# watch.net
KiCad netlist of a schematic drawn in EAGLE
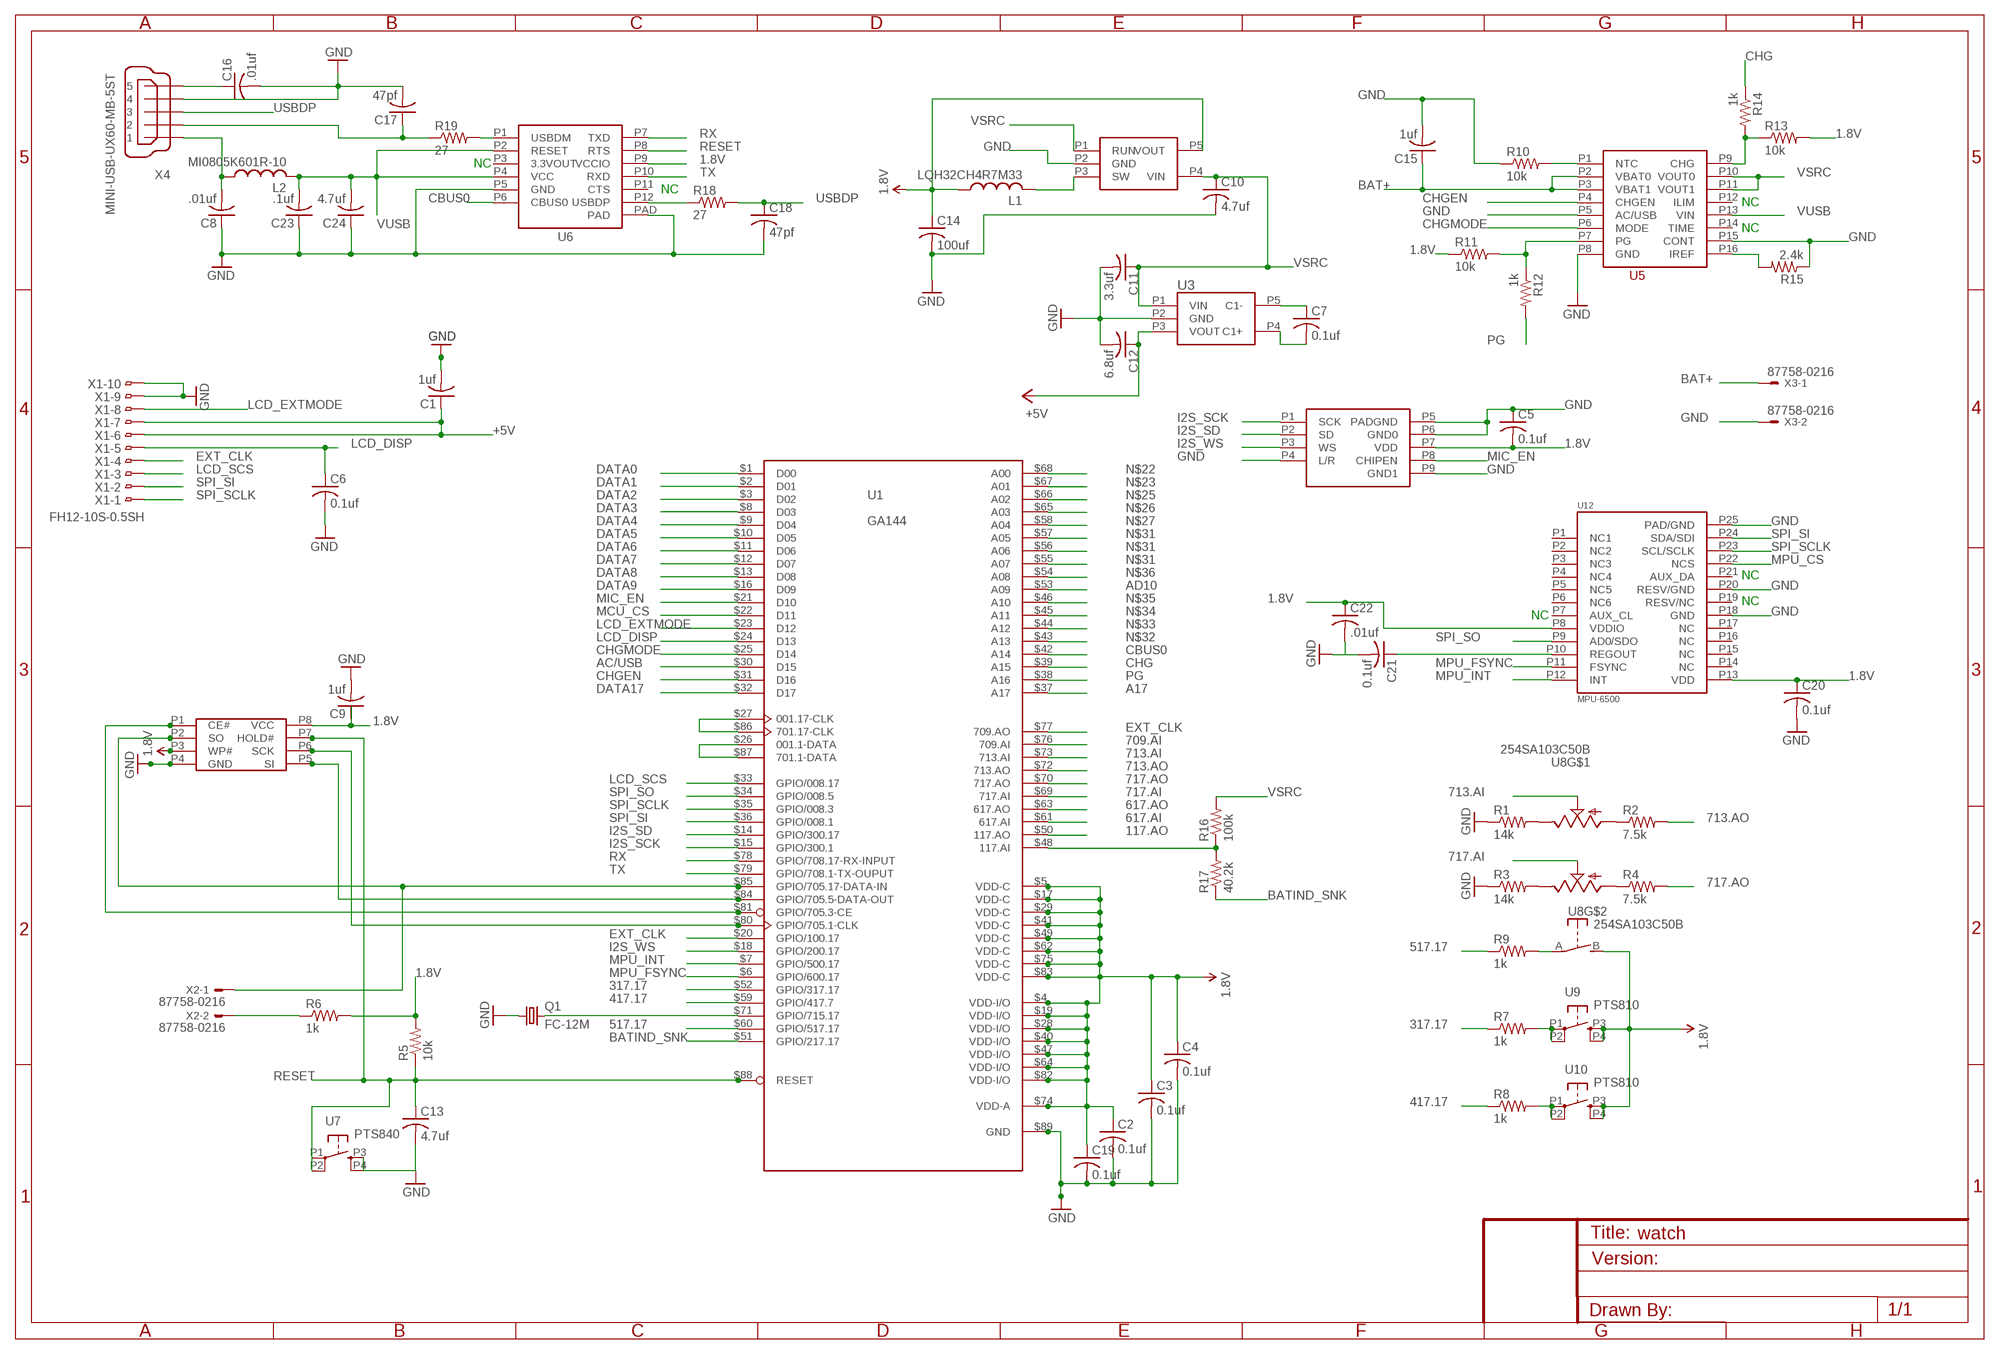
[diagram p0: schematic, sheet 1]

(export (version "E")
  (design (tool "Eeschema 10.0.6"))
  (components
    (comp (ref "C1")
      (value "1uf")
      (footprint "eagle-import:C0402")
      (libsource (lib "eagle-import") (part "resistor_C-USC0402"))
    )
    (comp (ref "C2")
      (value "0.1uf")
      (footprint "eagle-import:C0402")
      (libsource (lib "eagle-import") (part "resistor_C-USC0402"))
    )
    (comp (ref "C3")
      (value "0.1uf")
      (footprint "eagle-import:C0402")
      (libsource (lib "eagle-import") (part "resistor_C-USC0402"))
    )
    (comp (ref "C4")
      (value "0.1uf")
      (footprint "eagle-import:C0402")
      (libsource (lib "eagle-import") (part "resistor_C-USC0402"))
    )
    (comp (ref "C5")
      (value "0.1uf")
      (footprint "eagle-import:C0402")
      (libsource (lib "eagle-import") (part "resistor_C-USC0402"))
    )
    (comp (ref "C6")
      (value "0.1uf")
      (footprint "eagle-import:C0402")
      (libsource (lib "eagle-import") (part "resistor_C-USC0402"))
    )
    (comp (ref "C7")
      (value "0.1uf")
      (footprint "eagle-import:C0402")
      (libsource (lib "eagle-import") (part "resistor_C-USC0402"))
    )
    (comp (ref "C8")
      (value ".01uf")
      (footprint "eagle-import:C0402")
      (libsource (lib "eagle-import") (part "resistor_C-USC0402"))
    )
    (comp (ref "C9")
      (value "1uf")
      (footprint "eagle-import:C0402")
      (libsource (lib "eagle-import") (part "resistor_C-USC0402"))
    )
    (comp (ref "C10")
      (value "4.7uf")
      (footprint "eagle-import:C0603")
      (libsource (lib "eagle-import") (part "resistor_C-USC0603"))
    )
    (comp (ref "C11")
      (value "3.3uf")
      (footprint "eagle-import:C0603")
      (libsource (lib "eagle-import") (part "resistor_C-USC0603"))
    )
    (comp (ref "C12")
      (value "6.8uf")
      (footprint "eagle-import:C0805")
      (libsource (lib "eagle-import") (part "resistor_C-USC0805"))
    )
    (comp (ref "C13")
      (value "4.7uf")
      (footprint "eagle-import:C0603")
      (libsource (lib "eagle-import") (part "resistor_C-USC0603"))
    )
    (comp (ref "C14")
      (value "100uf")
      (footprint "eagle-import:C1206")
      (libsource (lib "eagle-import") (part "C-USC1206"))
    )
    (comp (ref "C15")
      (value "1uf")
      (footprint "eagle-import:C0402")
      (libsource (lib "eagle-import") (part "resistor_C-USC0402"))
    )
    (comp (ref "C16")
      (value ".01uf")
      (footprint "eagle-import:C0402")
      (libsource (lib "eagle-import") (part "resistor_C-USC0402"))
    )
    (comp (ref "C17")
      (value "47pf")
      (footprint "eagle-import:C0402")
      (libsource (lib "eagle-import") (part "resistor_C-USC0402"))
    )
    (comp (ref "C18")
      (value "47pf")
      (footprint "eagle-import:C0402")
      (libsource (lib "eagle-import") (part "resistor_C-USC0402"))
    )
    (comp (ref "C19")
      (value "0.1uf")
      (footprint "eagle-import:C0402")
      (libsource (lib "eagle-import") (part "resistor_C-USC0402"))
    )
    (comp (ref "C20")
      (value "0.1uf")
      (footprint "eagle-import:C0402")
      (libsource (lib "eagle-import") (part "resistor_C-USC0402"))
    )
    (comp (ref "C21")
      (value "0.1uf")
      (footprint "eagle-import:C0402")
      (libsource (lib "eagle-import") (part "resistor_C-USC0402"))
    )
    (comp (ref "C22")
      (value ".01uf")
      (footprint "eagle-import:C0402")
      (libsource (lib "eagle-import") (part "resistor_C-USC0402"))
    )
    (comp (ref "C23")
      (value ".1uf")
      (footprint "eagle-import:C0402")
      (libsource (lib "eagle-import") (part "resistor_C-USC0402"))
    )
    (comp (ref "C24")
      (value "4.7uf")
      (footprint "eagle-import:C0402")
      (libsource (lib "eagle-import") (part "resistor_C-USC0402"))
    )
    (comp (ref "L1")
      (value "LQH32CH4R7M33")
      (footprint "eagle-import:1210")
      (libsource (lib "eagle-import") (part "LQH32CH4R7M33"))
    )
    (comp (ref "L2")
      (value "MI0805K601R-10")
      (footprint "eagle-import:C0805")
      (libsource (lib "eagle-import") (part "MI0805K601R-10"))
    )
    (comp (ref "Q1")
      (value "FC-12M")
      (footprint "eagle-import:FC-12M")
      (libsource (lib "eagle-import") (part "FC-12M"))
    )
    (comp (ref "R1")
      (value "14k")
      (footprint "eagle-import:R0402")
      (libsource (lib "eagle-import") (part "R-US_R0402"))
    )
    (comp (ref "R2")
      (value "7.5k")
      (footprint "eagle-import:R0402")
      (libsource (lib "eagle-import") (part "R-US_R0402"))
    )
    (comp (ref "R3")
      (value "14k")
      (footprint "eagle-import:R0402")
      (libsource (lib "eagle-import") (part "R-US_R0402"))
    )
    (comp (ref "R4")
      (value "7.5k")
      (footprint "eagle-import:R0402")
      (libsource (lib "eagle-import") (part "R-US_R0402"))
    )
    (comp (ref "R5")
      (value "10k")
      (footprint "eagle-import:R0402")
      (libsource (lib "eagle-import") (part "R-US_R0402"))
    )
    (comp (ref "R6")
      (value "1k")
      (footprint "eagle-import:R0402")
      (libsource (lib "eagle-import") (part "R-US_R0402"))
    )
    (comp (ref "R7")
      (value "1k")
      (footprint "eagle-import:R0402")
      (libsource (lib "eagle-import") (part "R-US_R0402"))
    )
    (comp (ref "R8")
      (value "1k")
      (footprint "eagle-import:R0402")
      (libsource (lib "eagle-import") (part "R-US_R0402"))
    )
    (comp (ref "R9")
      (value "1k")
      (footprint "eagle-import:R0402")
      (libsource (lib "eagle-import") (part "R-US_R0402"))
    )
    (comp (ref "R10")
      (value "10k")
      (footprint "eagle-import:R0402")
      (libsource (lib "eagle-import") (part "R-US_R0402"))
    )
    (comp (ref "R11")
      (value "10k")
      (footprint "eagle-import:R0402")
      (libsource (lib "eagle-import") (part "R-US_R0402"))
    )
    (comp (ref "R12")
      (value "1k")
      (footprint "eagle-import:R0402")
      (libsource (lib "eagle-import") (part "R-US_R0402"))
    )
    (comp (ref "R13")
      (value "10k")
      (footprint "eagle-import:R0402")
      (libsource (lib "eagle-import") (part "R-US_R0402"))
    )
    (comp (ref "R14")
      (value "1k")
      (footprint "eagle-import:R0402")
      (libsource (lib "eagle-import") (part "R-US_R0402"))
    )
    (comp (ref "R15")
      (value "2.4k")
      (footprint "eagle-import:R0402")
      (libsource (lib "eagle-import") (part "R-US_R0402"))
    )
    (comp (ref "R16")
      (value "100k")
      (footprint "eagle-import:R0402")
      (libsource (lib "eagle-import") (part "R-US_R0402"))
    )
    (comp (ref "R17")
      (value "40.2k")
      (footprint "eagle-import:R0402")
      (libsource (lib "eagle-import") (part "R-US_R0402"))
    )
    (comp (ref "R18")
      (value "27")
      (footprint "eagle-import:R0402")
      (libsource (lib "eagle-import") (part "R-US_R0402"))
    )
    (comp (ref "R19")
      (value "27")
      (footprint "eagle-import:R0402")
      (libsource (lib "eagle-import") (part "R-US_R0402"))
    )
    (comp (ref "U1")
      (value "GA144")
      (footprint "eagle-import:QFN88-0.4MM")
      (libsource (lib "eagle-import") (part "GA144"))
    )
    (comp (ref "U2")
      (value "LTC3406-1.8")
      (footprint "eagle-import:TSOT23")
      (libsource (lib "eagle-import") (part "LTC3406-1.8"))
    )
    (comp (ref "U3")
      (value "LTC1517-5")
      (footprint "eagle-import:TSOT23")
      (libsource (lib "eagle-import") (part "LTC1517-5"))
    )
    (comp (ref "U4")
      (value "IS25WP128-JKLE")
      (footprint "eagle-import:WSON8")
      (libsource (lib "eagle-import") (part "IS25WP128-JKLE"))
    )
    (comp (ref "U5")
      (value "ISL9230")
      (footprint "eagle-import:16_LD_QFN")
      (libsource (lib "eagle-import") (part "ISL9230"))
    )
    (comp (ref "U6")
      (value "FT234XD")
      (footprint "eagle-import:DFN-12")
      (libsource (lib "eagle-import") (part "FT234XD"))
    )
    (comp (ref "U7")
      (value "PTS840")
      (footprint "eagle-import:PTS840GMPSMTRLFS")
      (libsource (lib "eagle-import") (part "PTS840"))
    )
    (comp (ref "U8")
      (value "254SA103C50B")
      (footprint "eagle-import:254SA103C50B")
      (libsource (lib "eagle-import") (part "254SA103C50B"))
    )
    (comp (ref "U9")
      (value "PTS810")
      (footprint "eagle-import:PTS810")
      (libsource (lib "eagle-import") (part "PTS810"))
    )
    (comp (ref "U10")
      (value "PTS810")
      (footprint "eagle-import:PTS810")
      (libsource (lib "eagle-import") (part "PTS810"))
    )
    (comp (ref "U11")
      (value "INMP441")
      (footprint "eagle-import:INMP441")
      (libsource (lib "eagle-import") (part "INMP441"))
    )
    (comp (ref "U12")
      (value "MPU-6500")
      (footprint "eagle-import:QFN24-3")
      (libsource (lib "eagle-import") (part "MPU-6500"))
    )
    (comp (ref "X1")
      (value "FH12-10S-0.5SH")
      (footprint "eagle-import:FH12-10S-0.5SH")
      (fields (field (name "MPN") "FH12-10S-0.5SH(55)"))
      (libsource (lib "eagle-import") (part "FH12-10S-0.5SH"))
    )
    (comp (ref "X2")
      (value "87758-0216")
      (footprint "eagle-import:87758-0216")
      (libsource (lib "eagle-import") (part "87758-0216"))
    )
    (comp (ref "X3")
      (value "87758-0216")
      (footprint "eagle-import:87758-0216")
      (libsource (lib "eagle-import") (part "87758-0216"))
    )
    (comp (ref "X4")
      (value "MINI-USB-UX60-MB-5ST")
      (footprint "eagle-import:UX60-MB-5ST")
      (libsource (lib "eagle-import") (part "MINI-USB-UX60-MB-5ST"))
    )
  )
  (nets
    (net (code "1") (name "+5V") (class "Default")
      (node (ref "C1") (pin "1") (pinfunction "1_1") (pintype "passive"))
      (node (ref "C12") (pin "1") (pinfunction "1_1") (pintype "passive"))
      (node (ref "U3") (pin "P3") (pinfunction "VOUT_P3") (pintype "bidirectional"))
      (node (ref "X1") (pin "6") (pinfunction "1_6") (pintype "passive"))
      (node (ref "X1") (pin "7") (pinfunction "1_7") (pintype "passive"))
    )
    (net (code "2") (name "/117.AO") (class "Default")
      (node (ref "U1") (pin "$50") (pinfunction "117.AO_$50") (pintype "output"))
    )
    (net (code "3") (name "/317.17") (class "Default")
      (node (ref "R7") (pin "1") (pinfunction "1_1") (pintype "passive"))
      (node (ref "U1") (pin "$52") (pinfunction "GPIO/317.17_$52") (pintype "bidirectional"))
    )
    (net (code "4") (name "/417.17") (class "Default")
      (node (ref "R8") (pin "1") (pinfunction "1_1") (pintype "passive"))
      (node (ref "U1") (pin "$59") (pinfunction "GPIO/417.7_$59") (pintype "bidirectional"))
    )
    (net (code "5") (name "/517.17") (class "Default")
      (node (ref "R9") (pin "1") (pinfunction "1_1") (pintype "passive"))
      (node (ref "U1") (pin "$60") (pinfunction "GPIO/517.17_$60") (pintype "bidirectional"))
    )
    (net (code "6") (name "/617.AI") (class "Default")
      (node (ref "U1") (pin "$61") (pinfunction "617.AI_$61") (pintype "input"))
    )
    (net (code "7") (name "/617.AO") (class "Default")
      (node (ref "U1") (pin "$63") (pinfunction "617.AO_$63") (pintype "output"))
    )
    (net (code "8") (name "/709.AI") (class "Default")
      (node (ref "U1") (pin "$76") (pinfunction "709.AI_$76") (pintype "input"))
    )
    (net (code "9") (name "/713.AI") (class "Default")
      (node (ref "U1") (pin "$73") (pinfunction "713.AI_$73") (pintype "input"))
      (node (ref "U8") (pin "P2") (pinfunction "P2_P2") (pintype "passive"))
    )
    (net (code "10") (name "/713.AO") (class "Default")
      (node (ref "R2") (pin "2") (pinfunction "2_2") (pintype "passive"))
      (node (ref "U1") (pin "$72") (pinfunction "713.AO_$72") (pintype "output"))
    )
    (net (code "11") (name "/717.AI") (class "Default")
      (node (ref "U1") (pin "$69") (pinfunction "717.AI_$69") (pintype "input"))
      (node (ref "U8") (pin "P2'") (pinfunction "P2'_P2'") (pintype "passive"))
    )
    (net (code "12") (name "/717.AO") (class "Default")
      (node (ref "R4") (pin "2") (pinfunction "2_2") (pintype "passive"))
      (node (ref "U1") (pin "$70") (pinfunction "717.AO_$70") (pintype "output"))
    )
    (net (code "13") (name "/A17") (class "Default")
      (node (ref "U1") (pin "$37") (pinfunction "A17_$37") (pintype "output"))
    )
    (net (code "14") (name "/AC{slash}USB") (class "Default")
      (node (ref "U1") (pin "$30") (pinfunction "D15_$30") (pintype "bidirectional"))
    )
    (net (code "15") (name "/AD10") (class "Default")
      (node (ref "U1") (pin "$53") (pinfunction "A09_$53") (pintype "output"))
    )
    (net (code "16") (name "/AUX_CL") (class "Default")
      (node (ref "U12") (pin "P7") (pinfunction "AUX_CL_P7") (pintype "power_in"))
    )
    (net (code "17") (name "/AUX_DA") (class "Default")
      (node (ref "U12") (pin "P21") (pinfunction "AUX_DA_P21") (pintype "power_in"))
    )
    (net (code "18") (name "/BAT+") (class "Default")
      (node (ref "C15") (pin "1") (pinfunction "1_1") (pintype "passive"))
      (node (ref "U5") (pin "P2") (pinfunction "VBAT0_P2") (pintype "bidirectional"))
      (node (ref "U5") (pin "P3") (pinfunction "VBAT1_P3") (pintype "bidirectional"))
      (node (ref "X3") (pin "1") (pinfunction "S_1") (pintype "passive"))
    )
    (net (code "19") (name "/BATIND_SNK") (class "Default")
      (node (ref "R17") (pin "1") (pinfunction "1_1") (pintype "passive"))
      (node (ref "U1") (pin "$51") (pinfunction "GPIO/217.17_$51") (pintype "bidirectional"))
    )
    (net (code "20") (name "/CBUS0") (class "Default")
      (node (ref "U1") (pin "$42") (pinfunction "A14_$42") (pintype "output"))
      (node (ref "U6") (pin "P6") (pinfunction "CBUS0_P6") (pintype "bidirectional"))
    )
    (net (code "21") (name "/CHG") (class "Default")
      (node (ref "R14") (pin "1") (pinfunction "1_1") (pintype "passive"))
      (node (ref "U1") (pin "$39") (pinfunction "A15_$39") (pintype "output"))
    )
    (net (code "22") (name "/CHGEN") (class "Default")
      (node (ref "U1") (pin "$31") (pinfunction "D16_$31") (pintype "bidirectional"))
      (node (ref "U5") (pin "P4") (pinfunction "CHGEN_P4") (pintype "bidirectional"))
    )
    (net (code "23") (name "/CHGMODE") (class "Default")
      (node (ref "U1") (pin "$25") (pinfunction "D14_$25") (pintype "bidirectional"))
      (node (ref "U5") (pin "P6") (pinfunction "MODE_P6") (pintype "bidirectional"))
    )
    (net (code "24") (name "/DATA0") (class "Default")
      (node (ref "U1") (pin "$1") (pinfunction "D00_$1") (pintype "bidirectional"))
    )
    (net (code "25") (name "/DATA1") (class "Default")
      (node (ref "U1") (pin "$2") (pinfunction "D01_$2") (pintype "bidirectional"))
    )
    (net (code "26") (name "/DATA2") (class "Default")
      (node (ref "U1") (pin "$3") (pinfunction "D02_$3") (pintype "bidirectional"))
    )
    (net (code "27") (name "/DATA3") (class "Default")
      (node (ref "U1") (pin "$8") (pinfunction "D03_$8") (pintype "bidirectional"))
    )
    (net (code "28") (name "/DATA4") (class "Default")
      (node (ref "U1") (pin "$9") (pinfunction "D04_$9") (pintype "bidirectional"))
    )
    (net (code "29") (name "/DATA5") (class "Default")
      (node (ref "U1") (pin "$10") (pinfunction "D05_$10") (pintype "bidirectional"))
    )
    (net (code "30") (name "/DATA6") (class "Default")
      (node (ref "U1") (pin "$11") (pinfunction "D06_$11") (pintype "bidirectional"))
    )
    (net (code "31") (name "/DATA7") (class "Default")
      (node (ref "U1") (pin "$12") (pinfunction "D07_$12") (pintype "bidirectional"))
    )
    (net (code "32") (name "/DATA8") (class "Default")
      (node (ref "U1") (pin "$13") (pinfunction "D08_$13") (pintype "bidirectional"))
    )
    (net (code "33") (name "/DATA9") (class "Default")
      (node (ref "U1") (pin "$16") (pinfunction "D09_$16") (pintype "bidirectional"))
    )
    (net (code "34") (name "/DATA17") (class "Default")
      (node (ref "U1") (pin "$32") (pinfunction "D17_$32") (pintype "bidirectional"))
    )
    (net (code "35") (name "/EXT_CLK") (class "Default")
      (node (ref "U1") (pin "$20") (pinfunction "GPIO/100.17_$20") (pintype "bidirectional"))
      (node (ref "U1") (pin "$77") (pinfunction "709.AO_$77") (pintype "output"))
      (node (ref "X1") (pin "4") (pinfunction "1_4") (pintype "passive"))
    )
    (net (code "36") (name "/I2S_SCK") (class "Default")
      (node (ref "U1") (pin "$15") (pinfunction "GPIO/300.1_$15") (pintype "bidirectional"))
      (node (ref "U11") (pin "P1") (pinfunction "SCK_P1") (pintype "bidirectional"))
    )
    (net (code "37") (name "/I2S_SD") (class "Default")
      (node (ref "U1") (pin "$14") (pinfunction "GPIO/300.17_$14") (pintype "bidirectional"))
      (node (ref "U11") (pin "P2") (pinfunction "SD_P2") (pintype "bidirectional"))
    )
    (net (code "38") (name "/I2S_WS") (class "Default")
      (node (ref "U1") (pin "$18") (pinfunction "GPIO/200.17_$18") (pintype "bidirectional"))
      (node (ref "U11") (pin "P3") (pinfunction "WS_P3") (pintype "bidirectional"))
    )
    (net (code "39") (name "/LCD_DISP") (class "Default")
      (node (ref "C6") (pin "1") (pinfunction "1_1") (pintype "passive"))
      (node (ref "U1") (pin "$24") (pinfunction "D13_$24") (pintype "bidirectional"))
      (node (ref "X1") (pin "5") (pinfunction "1_5") (pintype "passive"))
    )
    (net (code "40") (name "/LCD_EXTMODE") (class "Default")
      (node (ref "U1") (pin "$23") (pinfunction "D12_$23") (pintype "bidirectional"))
      (node (ref "X1") (pin "8") (pinfunction "1_8") (pintype "passive"))
    )
    (net (code "41") (name "/LCD_SCS") (class "Default")
      (node (ref "U1") (pin "$33") (pinfunction "GPIO/008.17_$33") (pintype "bidirectional"))
      (node (ref "X1") (pin "3") (pinfunction "1_3") (pintype "passive"))
    )
    (net (code "42") (name "/MCU_CS") (class "Default")
      (node (ref "U1") (pin "$22") (pinfunction "D11_$22") (pintype "bidirectional"))
    )
    (net (code "43") (name "/MIC_EN") (class "Default")
      (node (ref "U1") (pin "$21") (pinfunction "D10_$21") (pintype "bidirectional"))
      (node (ref "U11") (pin "P8") (pinfunction "CHIPEN_P8") (pintype "bidirectional"))
    )
    (net (code "44") (name "/MPU_CS") (class "Default")
      (node (ref "U12") (pin "P22") (pinfunction "NCS_P22") (pintype "power_in"))
    )
    (net (code "45") (name "/MPU_FSYNC") (class "Default")
      (node (ref "U1") (pin "$6") (pinfunction "GPIO/600.17_$6") (pintype "bidirectional"))
      (node (ref "U12") (pin "P11") (pinfunction "FSYNC_P11") (pintype "power_in"))
    )
    (net (code "46") (name "/MPU_INT") (class "Default")
      (node (ref "U1") (pin "$7") (pinfunction "GPIO/500.17_$7") (pintype "bidirectional"))
      (node (ref "U12") (pin "P12") (pinfunction "INT_P12") (pintype "power_in"))
    )
    (net (code "47") (name "/N$22") (class "Default")
      (node (ref "U1") (pin "$68") (pinfunction "A00_$68") (pintype "output"))
    )
    (net (code "48") (name "/N$23") (class "Default")
      (node (ref "U1") (pin "$67") (pinfunction "A01_$67") (pintype "output"))
    )
    (net (code "49") (name "/N$25") (class "Default")
      (node (ref "U1") (pin "$66") (pinfunction "A02_$66") (pintype "output"))
    )
    (net (code "50") (name "/N$26") (class "Default")
      (node (ref "U1") (pin "$65") (pinfunction "A03_$65") (pintype "output"))
    )
    (net (code "51") (name "/N$27") (class "Default")
      (node (ref "U1") (pin "$58") (pinfunction "A04_$58") (pintype "output"))
    )
    (net (code "52") (name "/N$31") (class "Default")
      (node (ref "U1") (pin "$55") (pinfunction "A07_$55") (pintype "output"))
    )
    (net (code "53") (name "/N$32") (class "Default")
      (node (ref "U1") (pin "$43") (pinfunction "A13_$43") (pintype "output"))
    )
    (net (code "54") (name "/N$33") (class "Default")
      (node (ref "U1") (pin "$44") (pinfunction "A12_$44") (pintype "output"))
    )
    (net (code "55") (name "/N$34") (class "Default")
      (node (ref "U1") (pin "$45") (pinfunction "A11_$45") (pintype "output"))
    )
    (net (code "56") (name "/N$35") (class "Default")
      (node (ref "U1") (pin "$46") (pinfunction "A10_$46") (pintype "output"))
    )
    (net (code "57") (name "/N$36") (class "Default")
      (node (ref "U1") (pin "$54") (pinfunction "A08_$54") (pintype "output"))
    )
    (net (code "58") (name "/PG") (class "Default")
      (node (ref "R12") (pin "2") (pinfunction "2_2") (pintype "passive"))
      (node (ref "U1") (pin "$38") (pinfunction "A16_$38") (pintype "output"))
    )
    (net (code "59") (name "/RESET") (class "Default")
      (node (ref "C13") (pin "1") (pinfunction "1_1") (pintype "passive"))
      (node (ref "R5") (pin "1") (pinfunction "1_1") (pintype "passive"))
      (node (ref "U1") (pin "$88") (pinfunction "RESET_$88") (pintype "bidirectional"))
      (node (ref "U4") (pin "P7") (pinfunction "HOLD#_P7") (pintype "bidirectional"))
      (node (ref "U6") (pin "P8") (pinfunction "RTS_P8") (pintype "bidirectional"))
      (node (ref "U7") (pin "P1") (pinfunction "P_P1") (pintype "passive"))
      (node (ref "U7") (pin "P2") (pinfunction "P1_P2") (pintype "passive"))
    )
    (net (code "60") (name "/RESV{slash}NC") (class "Default")
      (node (ref "U12") (pin "P19") (pinfunction "RESV/NC_P19") (pintype "power_in"))
    )
    (net (code "61") (name "/RX") (class "Default")
      (node (ref "U1") (pin "$78") (pinfunction "GPIO/708.17-RX-INPUT_$78") (pintype "input"))
      (node (ref "U6") (pin "P7") (pinfunction "TXD_P7") (pintype "bidirectional"))
    )
    (net (code "62") (name "/SPI_SCLK") (class "Default")
      (node (ref "U1") (pin "$35") (pinfunction "GPIO/008.3_$35") (pintype "bidirectional"))
      (node (ref "U12") (pin "P23") (pinfunction "SCL/SCLK_P23") (pintype "power_in"))
      (node (ref "X1") (pin "1") (pinfunction "1_1") (pintype "passive"))
    )
    (net (code "63") (name "/SPI_SI") (class "Default")
      (node (ref "U1") (pin "$36") (pinfunction "GPIO/008.1_$36") (pintype "bidirectional"))
      (node (ref "U12") (pin "P24") (pinfunction "SDA/SDI_P24") (pintype "power_in"))
      (node (ref "X1") (pin "2") (pinfunction "1_2") (pintype "passive"))
    )
    (net (code "64") (name "/SPI_SO") (class "Default")
      (node (ref "U1") (pin "$34") (pinfunction "GPIO/008.5_$34") (pintype "bidirectional"))
      (node (ref "U12") (pin "P9") (pinfunction "AD0/SDO_P9") (pintype "power_in"))
    )
    (net (code "65") (name "/TX") (class "Default")
      (node (ref "U1") (pin "$79") (pinfunction "GPIO/708.1-TX-OUPUT_$79") (pintype "output"))
      (node (ref "U6") (pin "P10") (pinfunction "RXD_P10") (pintype "bidirectional"))
    )
    (net (code "66") (name "/USBDM") (class "Default")
      (node (ref "C17") (pin "1") (pinfunction "1_1") (pintype "passive"))
      (node (ref "R19") (pin "1") (pinfunction "1_1") (pintype "passive"))
      (node (ref "R19") (pin "2") (pinfunction "2_2") (pintype "passive"))
      (node (ref "U6") (pin "P1") (pinfunction "USBDM_P1") (pintype "bidirectional"))
      (node (ref "X4") (pin "2") (pinfunction "2_2") (pintype "input"))
    )
    (net (code "67") (name "/USBDP") (class "Default")
      (node (ref "C18") (pin "1") (pinfunction "1_1") (pintype "passive"))
      (node (ref "R18") (pin "1") (pinfunction "1_1") (pintype "passive"))
      (node (ref "R18") (pin "2") (pinfunction "2_2") (pintype "passive"))
      (node (ref "U6") (pin "P12") (pinfunction "USBDP_P12") (pintype "bidirectional"))
      (node (ref "X4") (pin "3") (pinfunction "3_3") (pintype "input"))
    )
    (net (code "68") (name "/VSRC") (class "Default")
      (node (ref "C10") (pin "1") (pinfunction "1_1") (pintype "passive"))
      (node (ref "C11") (pin "1") (pinfunction "1_1") (pintype "passive"))
      (node (ref "R16") (pin "2") (pinfunction "2_2") (pintype "passive"))
      (node (ref "U2") (pin "P1") (pinfunction "RUN_P1") (pintype "bidirectional"))
      (node (ref "U2") (pin "P4") (pinfunction "VIN_P4") (pintype "bidirectional"))
      (node (ref "U3") (pin "P1") (pinfunction "VIN_P1") (pintype "bidirectional"))
      (node (ref "U5") (pin "P10") (pinfunction "VOUT0_P10") (pintype "bidirectional"))
      (node (ref "U5") (pin "P11") (pinfunction "VOUT1_P11") (pintype "bidirectional"))
    )
    (net (code "69") (name "/VUSB") (class "Default")
      (node (ref "C23") (pin "2") (pinfunction "2_2") (pintype "passive"))
      (node (ref "C24") (pin "2") (pinfunction "2_2") (pintype "passive"))
      (node (ref "C8") (pin "2") (pinfunction "2_2") (pintype "passive"))
      (node (ref "L2") (pin "1") (pinfunction "1_1") (pintype "passive"))
      (node (ref "L2") (pin "2") (pinfunction "2_2") (pintype "passive"))
      (node (ref "U5") (pin "P13") (pinfunction "VIN_P13") (pintype "bidirectional"))
      (node (ref "U6") (pin "P2") (pinfunction "RESET_P2") (pintype "bidirectional"))
      (node (ref "U6") (pin "P4") (pinfunction "VCC_P4") (pintype "bidirectional"))
      (node (ref "X4") (pin "1") (pinfunction "1_1") (pintype "input"))
    )
    (net (code "70") (name "1.8V") (class "Default")
      (node (ref "C14") (pin "1") (pinfunction "1_1") (pintype "passive"))
      (node (ref "C19") (pin "1") (pinfunction "1_1") (pintype "passive"))
      (node (ref "C2") (pin "1") (pinfunction "1_1") (pintype "passive"))
      (node (ref "C20") (pin "1") (pinfunction "1_1") (pintype "passive"))
      (node (ref "C22") (pin "1") (pinfunction "1_1") (pintype "passive"))
      (node (ref "C3") (pin "1") (pinfunction "1_1") (pintype "passive"))
      (node (ref "C4") (pin "1") (pinfunction "1_1") (pintype "passive"))
      (node (ref "C5") (pin "2") (pinfunction "2_2") (pintype "passive"))
      (node (ref "C9") (pin "1") (pinfunction "1_1") (pintype "passive"))
      (node (ref "L1") (pin "P$1") (pinfunction "1_P$1") (pintype "passive"))
      (node (ref "R11") (pin "1") (pinfunction "1_1") (pintype "passive"))
      (node (ref "R13") (pin "2") (pinfunction "2_2") (pintype "passive"))
      (node (ref "R5") (pin "2") (pinfunction "2_2") (pintype "passive"))
      (node (ref "R6") (pin "2") (pinfunction "2_2") (pintype "passive"))
      (node (ref "U1") (pin "$17") (pinfunction "VDD-C_$17") (pintype "power_in"))
      (node (ref "U1") (pin "$19") (pinfunction "VDD-I/O_$19") (pintype "bidirectional"))
      (node (ref "U1") (pin "$28") (pinfunction "VDD-I/O_$28") (pintype "bidirectional"))
      (node (ref "U1") (pin "$29") (pinfunction "VDD-C_$29") (pintype "bidirectional"))
      (node (ref "U1") (pin "$4") (pinfunction "VDD-I/O_$4") (pintype "power_in"))
      (node (ref "U1") (pin "$40") (pinfunction "VDD-I/O_$40") (pintype "bidirectional"))
      (node (ref "U1") (pin "$41") (pinfunction "VDD-C_$41") (pintype "bidirectional"))
      (node (ref "U1") (pin "$47") (pinfunction "VDD-I/O_$47") (pintype "bidirectional"))
      (node (ref "U1") (pin "$49") (pinfunction "VDD-C_$49") (pintype "bidirectional"))
      (node (ref "U1") (pin "$5") (pinfunction "VDD-C_$5") (pintype "power_in"))
      (node (ref "U1") (pin "$62") (pinfunction "VDD-C_$62") (pintype "bidirectional"))
      (node (ref "U1") (pin "$64") (pinfunction "VDD-I/O_$64") (pintype "bidirectional"))
      (node (ref "U1") (pin "$74") (pinfunction "VDD-A_$74") (pintype "power_in"))
      (node (ref "U1") (pin "$75") (pinfunction "VDD-C_$75") (pintype "bidirectional"))
      (node (ref "U1") (pin "$82") (pinfunction "VDD-I/O_$82") (pintype "bidirectional"))
      (node (ref "U1") (pin "$83") (pinfunction "VDD-C_$83") (pintype "bidirectional"))
      (node (ref "U10") (pin "P3") (pinfunction "S_P3") (pintype "passive"))
      (node (ref "U10") (pin "P4") (pinfunction "S1_P4") (pintype "passive"))
      (node (ref "U11") (pin "P7") (pinfunction "VDD_P7") (pintype "bidirectional"))
      (node (ref "U12") (pin "P13") (pinfunction "VDD_P13") (pintype "power_in"))
      (node (ref "U12") (pin "P8") (pinfunction "VDDIO_P8") (pintype "power_in"))
      (node (ref "U2") (pin "P5") (pinfunction "VOUT_P5") (pintype "bidirectional"))
      (node (ref "U4") (pin "P3") (pinfunction "WP#_P3") (pintype "bidirectional"))
      (node (ref "U4") (pin "P8") (pinfunction "VCC_P8") (pintype "bidirectional"))
      (node (ref "U6") (pin "P9") (pinfunction "VCCIO_P9") (pintype "bidirectional"))
      (node (ref "U8") (pin "B") (pinfunction "B_B") (pintype "passive"))
      (node (ref "U9") (pin "P3") (pinfunction "S_P3") (pintype "passive"))
      (node (ref "U9") (pin "P4") (pinfunction "S1_P4") (pintype "passive"))
    )
    (net (code "71") (name "GND") (class "Default")
      (node (ref "C1") (pin "2") (pinfunction "2_2") (pintype "passive"))
      (node (ref "C10") (pin "2") (pinfunction "2_2") (pintype "passive"))
      (node (ref "C11") (pin "2") (pinfunction "2_2") (pintype "passive"))
      (node (ref "C12") (pin "2") (pinfunction "2_2") (pintype "passive"))
      (node (ref "C13") (pin "2") (pinfunction "2_2") (pintype "passive"))
      (node (ref "C14") (pin "2") (pinfunction "2_2") (pintype "passive"))
      (node (ref "C15") (pin "2") (pinfunction "2_2") (pintype "passive"))
      (node (ref "C16") (pin "2") (pinfunction "2_2") (pintype "passive"))
      (node (ref "C17") (pin "2") (pinfunction "2_2") (pintype "passive"))
      (node (ref "C18") (pin "2") (pinfunction "2_2") (pintype "passive"))
      (node (ref "C19") (pin "2") (pinfunction "2_2") (pintype "passive"))
      (node (ref "C2") (pin "2") (pinfunction "2_2") (pintype "passive"))
      (node (ref "C20") (pin "2") (pinfunction "2_2") (pintype "passive"))
      (node (ref "C21") (pin "2") (pinfunction "2_2") (pintype "passive"))
      (node (ref "C22") (pin "2") (pinfunction "2_2") (pintype "passive"))
      (node (ref "C23") (pin "1") (pinfunction "1_1") (pintype "passive"))
      (node (ref "C24") (pin "1") (pinfunction "1_1") (pintype "passive"))
      (node (ref "C3") (pin "2") (pinfunction "2_2") (pintype "passive"))
      (node (ref "C4") (pin "2") (pinfunction "2_2") (pintype "passive"))
      (node (ref "C5") (pin "1") (pinfunction "1_1") (pintype "passive"))
      (node (ref "C6") (pin "2") (pinfunction "2_2") (pintype "passive"))
      (node (ref "C8") (pin "1") (pinfunction "1_1") (pintype "passive"))
      (node (ref "C9") (pin "2") (pinfunction "2_2") (pintype "passive"))
      (node (ref "Q1") (pin "1") (pinfunction "1_1") (pintype "passive"))
      (node (ref "R1") (pin "1") (pinfunction "1_1") (pintype "passive"))
      (node (ref "R10") (pin "1") (pinfunction "1_1") (pintype "passive"))
      (node (ref "R15") (pin "1") (pinfunction "1_1") (pintype "passive"))
      (node (ref "R3") (pin "1") (pinfunction "1_1") (pintype "passive"))
      (node (ref "U1") (pin "$89") (pinfunction "GND_$89") (pintype "power_in"))
      (node (ref "U11") (pin "P4") (pinfunction "L/R_P4") (pintype "bidirectional"))
      (node (ref "U11") (pin "P5") (pinfunction "PADGND_P5") (pintype "bidirectional"))
      (node (ref "U11") (pin "P6") (pinfunction "GND0_P6") (pintype "bidirectional"))
      (node (ref "U11") (pin "P9") (pinfunction "GND1_P9") (pintype "bidirectional"))
      (node (ref "U12") (pin "P18") (pinfunction "GND_P18") (pintype "power_in"))
      (node (ref "U12") (pin "P20") (pinfunction "RESV/GND_P20") (pintype "power_in"))
      (node (ref "U12") (pin "P25") (pinfunction "PAD/GND_P25") (pintype "bidirectional"))
      (node (ref "U2") (pin "P2") (pinfunction "GND_P2") (pintype "bidirectional"))
      (node (ref "U3") (pin "P2") (pinfunction "GND_P2") (pintype "bidirectional"))
      (node (ref "U4") (pin "P4") (pinfunction "GND_P4") (pintype "bidirectional"))
      (node (ref "U5") (pin "P15") (pinfunction "CONT_P15") (pintype "bidirectional"))
      (node (ref "U5") (pin "P5") (pinfunction "AC/USB_P5") (pintype "bidirectional"))
      (node (ref "U5") (pin "P8") (pinfunction "GND_P8") (pintype "bidirectional"))
      (node (ref "U6") (pin "P5") (pinfunction "GND_P5") (pintype "bidirectional"))
      (node (ref "U6") (pin "PAD") (pinfunction "PAD_PAD") (pintype "bidirectional"))
      (node (ref "U7") (pin "P3") (pinfunction "S_P3") (pintype "passive"))
      (node (ref "U7") (pin "P4") (pinfunction "S1_P4") (pintype "passive"))
      (node (ref "X1") (pin "10") (pinfunction "1_10") (pintype "passive"))
      (node (ref "X1") (pin "9") (pinfunction "1_9") (pintype "passive"))
      (node (ref "X3") (pin "2") (pinfunction "S_2") (pintype "passive"))
      (node (ref "X4") (pin "4") (pinfunction "4_4") (pintype "input"))
    )
    (net (code "72") (name "Net-(C16-Pad1)") (class "Default")
      (node (ref "C16") (pin "1") (pinfunction "1_1") (pintype "passive"))
      (node (ref "X4") (pin "5") (pinfunction "5_5") (pintype "input"))
    )
    (net (code "73") (name "Net-(L1-2)") (class "Default")
      (node (ref "L1") (pin "P$2") (pinfunction "2_P$2") (pintype "passive"))
      (node (ref "U2") (pin "P3") (pinfunction "SW_P3") (pintype "bidirectional"))
    )
    (net (code "74") (name "Net-(R1-Pad2)") (class "Default")
      (node (ref "R1") (pin "2") (pinfunction "2_2") (pintype "passive"))
      (node (ref "U8") (pin "P1") (pinfunction "P1_P1") (pintype "passive"))
    )
    (net (code "75") (name "Net-(R2-Pad1)") (class "Default")
      (node (ref "R2") (pin "1") (pinfunction "1_1") (pintype "passive"))
      (node (ref "U8") (pin "P3") (pinfunction "P3_P3") (pintype "passive"))
    )
    (net (code "76") (name "Net-(R3-Pad2)") (class "Default")
      (node (ref "R3") (pin "2") (pinfunction "2_2") (pintype "passive"))
      (node (ref "U8") (pin "P1'") (pinfunction "P1'_P1'") (pintype "passive"))
    )
    (net (code "77") (name "Net-(R4-Pad1)") (class "Default")
      (node (ref "R4") (pin "1") (pinfunction "1_1") (pintype "passive"))
      (node (ref "U8") (pin "P3'") (pinfunction "P3'_P3'") (pintype "passive"))
    )
    (net (code "78") (name "Net-(R9-Pad2)") (class "Default")
      (node (ref "R9") (pin "2") (pinfunction "2_2") (pintype "passive"))
      (node (ref "U8") (pin "A") (pinfunction "A_A") (pintype "passive"))
    )
    (net (code "79") (name "Net-(U1-001.1-DATA)") (class "Default")
      (node (ref "U1") (pin "$26") (pinfunction "001.1-DATA_$26") (pintype "bidirectional"))
      (node (ref "U1") (pin "$87") (pinfunction "701.1-DATA_$87") (pintype "bidirectional"))
    )
    (net (code "80") (name "Net-(U1-001.17-CLK)") (class "Default")
      (node (ref "U1") (pin "$27") (pinfunction "001.17-CLK_$27") (pintype "output"))
      (node (ref "U1") (pin "$86") (pinfunction "701.17-CLK_$86") (pintype "output"))
    )
    (net (code "81") (name "Net-(U1-117.AI)") (class "Default")
      (node (ref "R16") (pin "1") (pinfunction "1_1") (pintype "passive"))
      (node (ref "R17") (pin "2") (pinfunction "2_2") (pintype "passive"))
      (node (ref "U1") (pin "$48") (pinfunction "117.AI_$48") (pintype "input"))
    )
    (net (code "82") (name "Net-(U1-GPIO{slash}705.1-CLK)") (class "Default")
      (node (ref "U1") (pin "$80") (pinfunction "GPIO/705.1-CLK_$80") (pintype "output"))
      (node (ref "U4") (pin "P6") (pinfunction "SCK_P6") (pintype "bidirectional"))
    )
    (net (code "83") (name "Net-(U1-GPIO{slash}705.3-CE)") (class "Default")
      (node (ref "U1") (pin "$81") (pinfunction "GPIO/705.3-CE_$81") (pintype "output"))
      (node (ref "U4") (pin "P1") (pinfunction "CE#_P1") (pintype "bidirectional"))
    )
    (net (code "84") (name "Net-(U1-GPIO{slash}705.5-DATA-OUT)") (class "Default")
      (node (ref "U1") (pin "$84") (pinfunction "GPIO/705.5-DATA-OUT_$84") (pintype "output"))
      (node (ref "U4") (pin "P5") (pinfunction "SI_P5") (pintype "bidirectional"))
    )
    (net (code "85") (name "Net-(U1-GPIO{slash}705.17-DATA-IN)") (class "Default")
      (node (ref "U1") (pin "$85") (pinfunction "GPIO/705.17-DATA-IN_$85") (pintype "input"))
      (node (ref "U4") (pin "P2") (pinfunction "SO_P2") (pintype "bidirectional"))
      (node (ref "X2") (pin "1") (pinfunction "S_1") (pintype "passive"))
    )
    (net (code "86") (name "Net-(U1-GPIO{slash}715.17)") (class "Default")
      (node (ref "Q1") (pin "2") (pinfunction "2_2") (pintype "passive"))
      (node (ref "U1") (pin "$71") (pinfunction "GPIO/715.17_$71") (pintype "bidirectional"))
    )
    (net (code "87") (name "Net-(U3-C1+)") (class "Default")
      (node (ref "C7") (pin "2") (pinfunction "2_2") (pintype "passive"))
      (node (ref "U3") (pin "P4") (pinfunction "C1+_P4") (pintype "bidirectional"))
    )
    (net (code "88") (name "Net-(U3-C1-)") (class "Default")
      (node (ref "C7") (pin "1") (pinfunction "1_1") (pintype "passive"))
      (node (ref "U3") (pin "P5") (pinfunction "C1-_P5") (pintype "bidirectional"))
    )
    (net (code "89") (name "Net-(U5-CHG)") (class "Default")
      (node (ref "R13") (pin "1") (pinfunction "1_1") (pintype "passive"))
      (node (ref "R14") (pin "2") (pinfunction "2_2") (pintype "passive"))
      (node (ref "U5") (pin "P9") (pinfunction "CHG_P9") (pintype "bidirectional"))
    )
    (net (code "90") (name "Net-(U5-IREF)") (class "Default")
      (node (ref "R15") (pin "2") (pinfunction "2_2") (pintype "passive"))
      (node (ref "U5") (pin "P16") (pinfunction "IREF_P16") (pintype "bidirectional"))
    )
    (net (code "91") (name "Net-(U5-NTC)") (class "Default")
      (node (ref "R10") (pin "2") (pinfunction "2_2") (pintype "passive"))
      (node (ref "U5") (pin "P1") (pinfunction "NTC_P1") (pintype "bidirectional"))
    )
    (net (code "92") (name "Net-(U5-PG)") (class "Default")
      (node (ref "R11") (pin "2") (pinfunction "2_2") (pintype "passive"))
      (node (ref "R12") (pin "1") (pinfunction "1_1") (pintype "passive"))
      (node (ref "U5") (pin "P7") (pinfunction "PG_P7") (pintype "bidirectional"))
    )
    (net (code "93") (name "Net-(U9-P)") (class "Default")
      (node (ref "R7") (pin "2") (pinfunction "2_2") (pintype "passive"))
      (node (ref "U9") (pin "P1") (pinfunction "P_P1") (pintype "passive"))
      (node (ref "U9") (pin "P2") (pinfunction "P1_P2") (pintype "passive"))
    )
    (net (code "94") (name "Net-(U10-P)") (class "Default")
      (node (ref "R8") (pin "2") (pinfunction "2_2") (pintype "passive"))
      (node (ref "U10") (pin "P1") (pinfunction "P_P1") (pintype "passive"))
      (node (ref "U10") (pin "P2") (pinfunction "P1_P2") (pintype "passive"))
    )
    (net (code "95") (name "Net-(U12-REGOUT)") (class "Default")
      (node (ref "C21") (pin "1") (pinfunction "1_1") (pintype "passive"))
      (node (ref "U12") (pin "P10") (pinfunction "REGOUT_P10") (pintype "power_in"))
    )
    (net (code "96") (name "Net-(X2B-S)") (class "Default")
      (node (ref "R6") (pin "1") (pinfunction "1_1") (pintype "passive"))
      (node (ref "X2") (pin "2") (pinfunction "S_2") (pintype "passive"))
    )
    (net (code "97") (name "unconnected-(U1-A05-Pad$57)") (class "Default")
      (node (ref "U1") (pin "$57") (pinfunction "A05_$57") (pintype "output"))
    )
    (net (code "98") (name "unconnected-(U1-A06-Pad$56)") (class "Default")
      (node (ref "U1") (pin "$56") (pinfunction "A06_$56") (pintype "output"))
    )
    (net (code "99") (name "unconnected-(U5-ILIM-PadP12)") (class "Default")
      (node (ref "U5") (pin "P12") (pinfunction "ILIM_P12") (pintype "bidirectional"))
    )
    (net (code "100") (name "unconnected-(U5-TIME-PadP14)") (class "Default")
      (node (ref "U5") (pin "P14") (pinfunction "TIME_P14") (pintype "bidirectional"))
    )
    (net (code "101") (name "unconnected-(U6-3.3VOUT-PadP3)") (class "Default")
      (node (ref "U6") (pin "P3") (pinfunction "3.3VOUT_P3") (pintype "bidirectional"))
    )
    (net (code "102") (name "unconnected-(U6-CTS-PadP11)") (class "Default")
      (node (ref "U6") (pin "P11") (pinfunction "CTS_P11") (pintype "bidirectional"))
    )
    (net (code "103") (name "unconnected-(U12-NC-PadP14)") (class "Default")
      (node (ref "U12") (pin "P14") (pinfunction "NC_P14") (pintype "no_connect"))
    )
    (net (code "104") (name "unconnected-(U12-NC-PadP15)") (class "Default")
      (node (ref "U12") (pin "P15") (pinfunction "NC_P15") (pintype "no_connect"))
    )
    (net (code "105") (name "unconnected-(U12-NC-PadP16)") (class "Default")
      (node (ref "U12") (pin "P16") (pinfunction "NC_P16") (pintype "no_connect"))
    )
    (net (code "106") (name "unconnected-(U12-NC-PadP17)") (class "Default")
      (node (ref "U12") (pin "P17") (pinfunction "NC_P17") (pintype "no_connect"))
    )
    (net (code "107") (name "unconnected-(U12-NC1-PadP1)") (class "Default")
      (node (ref "U12") (pin "P1") (pinfunction "NC1_P1") (pintype "input"))
    )
    (net (code "108") (name "unconnected-(U12-NC2-PadP2)") (class "Default")
      (node (ref "U12") (pin "P2") (pinfunction "NC2_P2") (pintype "no_connect"))
    )
    (net (code "109") (name "unconnected-(U12-NC3-PadP3)") (class "Default")
      (node (ref "U12") (pin "P3") (pinfunction "NC3_P3") (pintype "no_connect"))
    )
    (net (code "110") (name "unconnected-(U12-NC4-PadP4)") (class "Default")
      (node (ref "U12") (pin "P4") (pinfunction "NC4_P4") (pintype "no_connect"))
    )
    (net (code "111") (name "unconnected-(U12-NC5-PadP5)") (class "Default")
      (node (ref "U12") (pin "P5") (pinfunction "NC5_P5") (pintype "no_connect"))
    )
    (net (code "112") (name "unconnected-(U12-NC6-PadP6)") (class "Default")
      (node (ref "U12") (pin "P6") (pinfunction "NC6_P6") (pintype "no_connect"))
    )
  )
)
